# Antilog-NPNO.net
KiCad netlist of a schematic drawn in EAGLE
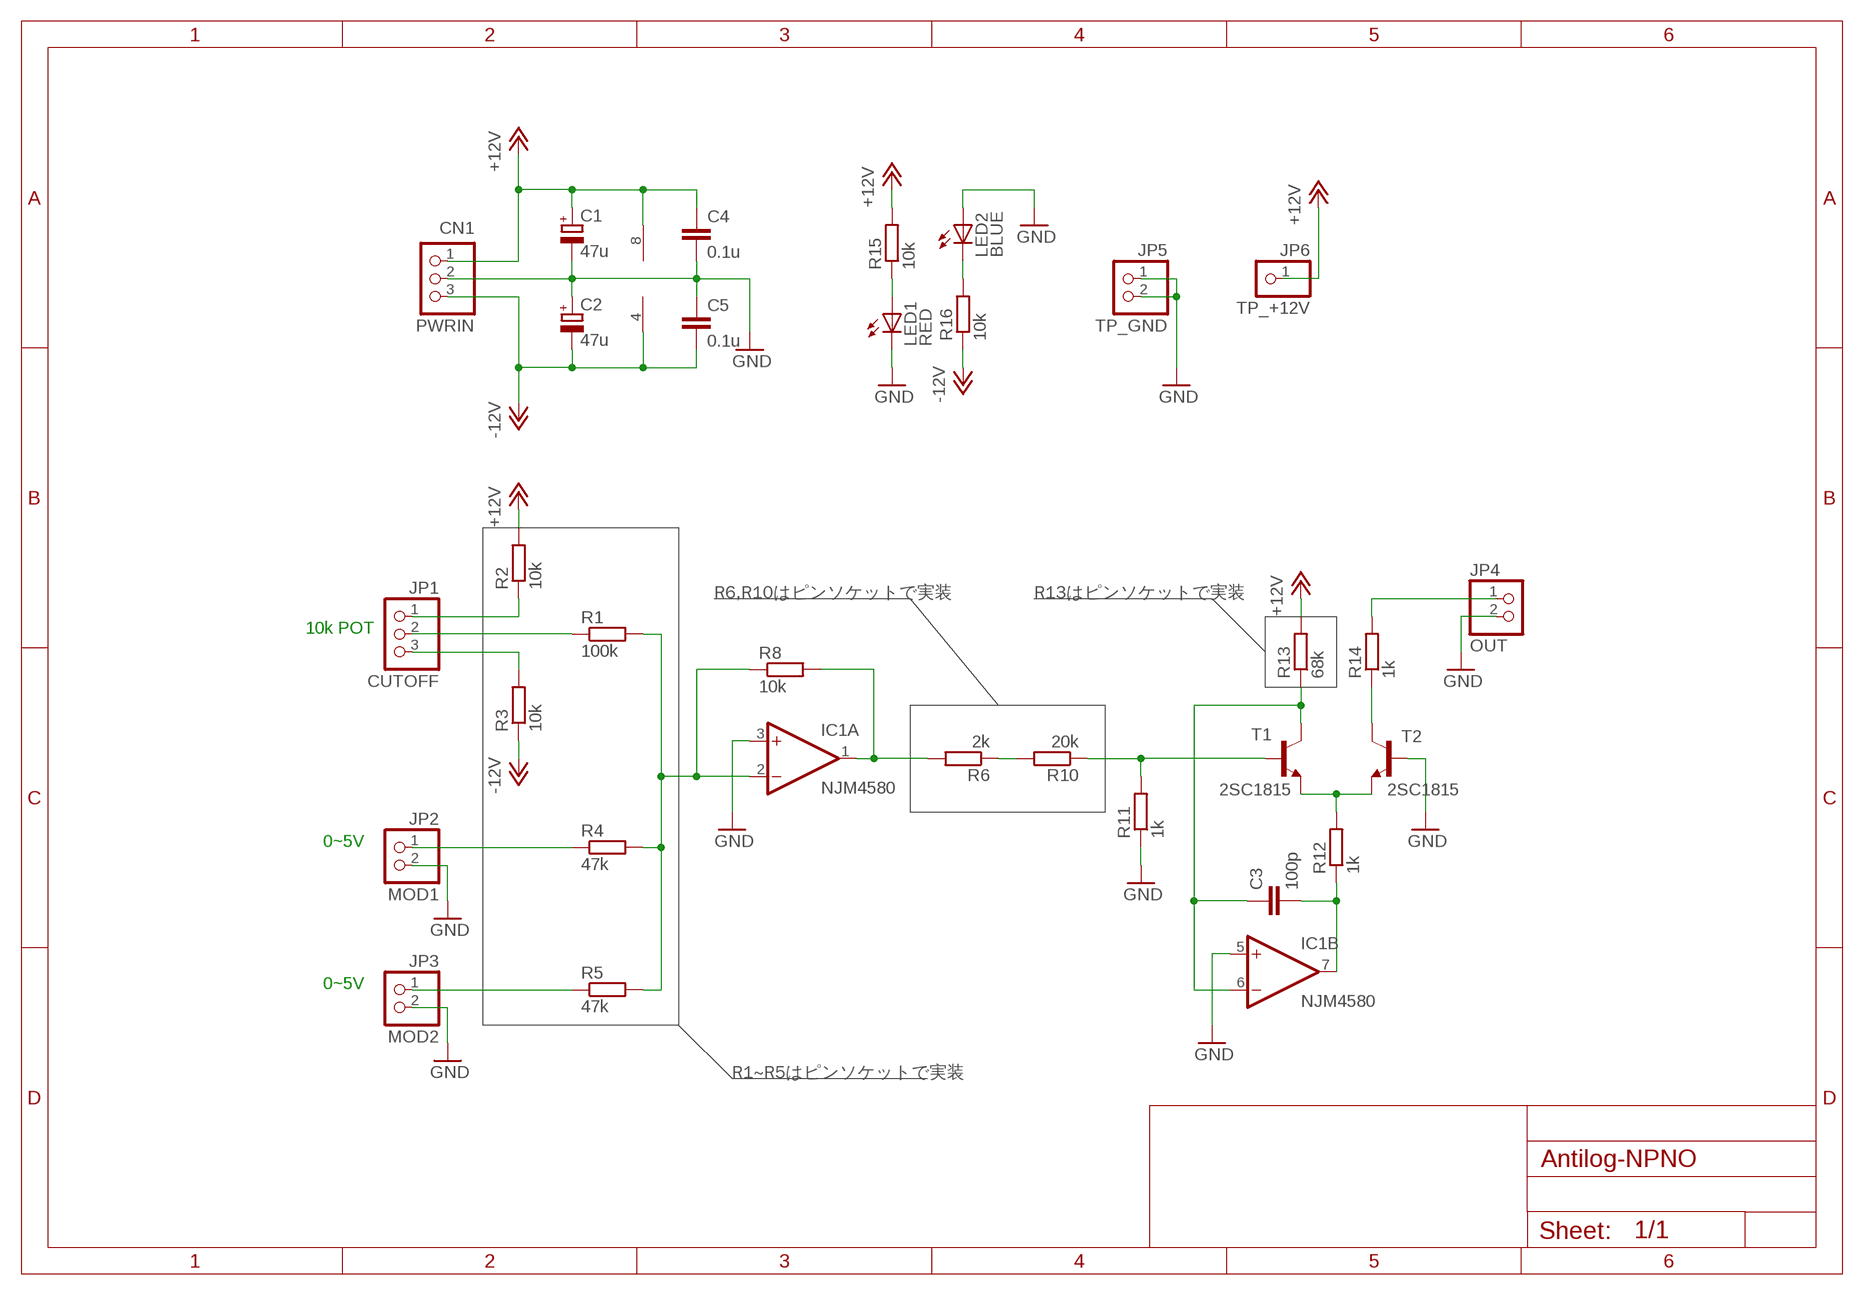
[diagram p0: schematic, sheet 1]

(export (version "E")
  (design (tool "Eeschema 10.0.6"))
  (components
    (comp (ref "C1")
      (value "47u")
      (footprint "eagle-import:E2,5-6")
      (libsource (lib "eagle-import") (part "CPOL-EUE2.5-6"))
    )
    (comp (ref "C2")
      (value "47u")
      (footprint "eagle-import:E2,5-6")
      (libsource (lib "eagle-import") (part "CPOL-EUE2.5-6"))
    )
    (comp (ref "C3")
      (value "100p")
      (footprint "eagle-import:C050-024X044")
      (libsource (lib "eagle-import") (part "C-EU050-024X044"))
    )
    (comp (ref "C4")
      (value "0.1u")
      (footprint "eagle-import:C025-024X044")
      (libsource (lib "eagle-import") (part "C-EU025-024X044"))
    )
    (comp (ref "C5")
      (value "0.1u")
      (footprint "eagle-import:C025-024X044")
      (libsource (lib "eagle-import") (part "C-EU025-024X044"))
    )
    (comp (ref "CN1")
      (value "PWRIN")
      (footprint "eagle-import:B3B-XH-A")
      (libsource (lib "eagle-import") (part "B3B-XH-A"))
    )
    (comp (ref "IC1")
      (value "NJM4580")
      (footprint "eagle-import:DIL08")
      (libsource (lib "eagle-import") (part "4558NLM"))
    )
    (comp (ref "JP1")
      (value "CUTOFF")
      (footprint "eagle-import:1X03")
      (libsource (lib "eagle-import") (part "PINHD-1X3"))
    )
    (comp (ref "JP2")
      (value "MOD1")
      (footprint "eagle-import:1X02")
      (libsource (lib "eagle-import") (part "PINHD-1X2"))
    )
    (comp (ref "JP3")
      (value "MOD2")
      (footprint "eagle-import:1X02")
      (libsource (lib "eagle-import") (part "PINHD-1X2"))
    )
    (comp (ref "JP4")
      (value "OUT")
      (footprint "eagle-import:1X02")
      (libsource (lib "eagle-import") (part "PINHD-1X2"))
    )
    (comp (ref "JP5")
      (value "TP_GND")
      (footprint "eagle-import:1X02")
      (libsource (lib "eagle-import") (part "PINHD-1X2"))
    )
    (comp (ref "JP6")
      (value "TP_+12V")
      (footprint "eagle-import:1X01")
      (libsource (lib "eagle-import") (part "PINHD-1X1"))
    )
    (comp (ref "LED1")
      (value "RED")
      (footprint "eagle-import:LED3MM")
      (libsource (lib "eagle-import") (part "LED3MM"))
    )
    (comp (ref "LED2")
      (value "BLUE")
      (footprint "eagle-import:LED3MM")
      (libsource (lib "eagle-import") (part "LED3MM"))
    )
    (comp (ref "R1")
      (value "100k")
      (footprint "eagle-import:0207_7")
      (libsource (lib "eagle-import") (part "R-EU_0207/7"))
    )
    (comp (ref "R2")
      (value "10k")
      (footprint "eagle-import:0207_7")
      (libsource (lib "eagle-import") (part "R-EU_0207/7"))
    )
    (comp (ref "R3")
      (value "10k")
      (footprint "eagle-import:0207_7")
      (libsource (lib "eagle-import") (part "R-EU_0207/7"))
    )
    (comp (ref "R4")
      (value "47k")
      (footprint "eagle-import:0207_7")
      (libsource (lib "eagle-import") (part "R-EU_0207/7"))
    )
    (comp (ref "R5")
      (value "47k")
      (footprint "eagle-import:0207_7")
      (libsource (lib "eagle-import") (part "R-EU_0207/7"))
    )
    (comp (ref "R6")
      (value "2k")
      (footprint "eagle-import:0207_7")
      (libsource (lib "eagle-import") (part "R-EU_0207/7"))
    )
    (comp (ref "R8")
      (value "10k")
      (footprint "eagle-import:0207_7")
      (libsource (lib "eagle-import") (part "R-EU_0207/7"))
    )
    (comp (ref "R10")
      (value "20k")
      (footprint "eagle-import:0207_7")
      (libsource (lib "eagle-import") (part "R-EU_0207/7"))
    )
    (comp (ref "R11")
      (value "1k")
      (footprint "eagle-import:0207_7")
      (libsource (lib "eagle-import") (part "R-EU_0207/7"))
    )
    (comp (ref "R12")
      (value "1k")
      (footprint "eagle-import:0207_7")
      (libsource (lib "eagle-import") (part "R-EU_0207/7"))
    )
    (comp (ref "R13")
      (value "68k")
      (footprint "eagle-import:0207_7")
      (libsource (lib "eagle-import") (part "R-EU_0207/7"))
    )
    (comp (ref "R14")
      (value "1k")
      (footprint "eagle-import:0207_7")
      (libsource (lib "eagle-import") (part "R-EU_0207/7"))
    )
    (comp (ref "R15")
      (value "10k")
      (footprint "eagle-import:0207_7")
      (libsource (lib "eagle-import") (part "R-EU_0207/7"))
    )
    (comp (ref "R16")
      (value "10k")
      (footprint "eagle-import:0207_7")
      (libsource (lib "eagle-import") (part "R-EU_0207/7"))
    )
    (comp (ref "T1")
      (value "2SC1815")
      (footprint "eagle-import:TO92-ECB")
      (libsource (lib "eagle-import") (part "-NPN-TO92-ECBBC368"))
    )
    (comp (ref "T2")
      (value "2SC1815")
      (footprint "eagle-import:TO92-ECB")
      (libsource (lib "eagle-import") (part "-NPN-TO92-ECBBC368"))
    )
  )
  (nets
    (net (code "1") (name "+12V") (class "Default")
      (node (ref "C1") (pin "+") (pinfunction "+_+") (pintype "passive"))
      (node (ref "C4") (pin "1") (pinfunction "1_1") (pintype "passive"))
      (node (ref "CN1") (pin "1") (pinfunction "1_1") (pintype "passive"))
      (node (ref "IC1") (pin "8") (pinfunction "V+_8") (pintype "power_in"))
      (node (ref "JP6") (pin "1") (pinfunction "1_1") (pintype "passive"))
      (node (ref "R13") (pin "2") (pinfunction "2_2") (pintype "passive"))
      (node (ref "R15") (pin "2") (pinfunction "2_2") (pintype "passive"))
      (node (ref "R2") (pin "2") (pinfunction "2_2") (pintype "passive"))
    )
    (net (code "2") (name "-12V") (class "Default")
      (node (ref "C2") (pin "-") (pinfunction "-_-") (pintype "passive"))
      (node (ref "C5") (pin "2") (pinfunction "2_2") (pintype "passive"))
      (node (ref "CN1") (pin "3") (pinfunction "3_3") (pintype "passive"))
      (node (ref "IC1") (pin "4") (pinfunction "V-_4") (pintype "power_in"))
      (node (ref "R16") (pin "1") (pinfunction "1_1") (pintype "passive"))
      (node (ref "R3") (pin "1") (pinfunction "1_1") (pintype "passive"))
    )
    (net (code "3") (name "GND") (class "Default")
      (node (ref "C1") (pin "-") (pinfunction "-_-") (pintype "passive"))
      (node (ref "C2") (pin "+") (pinfunction "+_+") (pintype "passive"))
      (node (ref "C4") (pin "2") (pinfunction "2_2") (pintype "passive"))
      (node (ref "C5") (pin "1") (pinfunction "1_1") (pintype "passive"))
      (node (ref "CN1") (pin "2") (pinfunction "2_2") (pintype "passive"))
      (node (ref "IC1") (pin "3") (pinfunction "+IN_3") (pintype "input"))
      (node (ref "IC1") (pin "5") (pinfunction "+IN_5") (pintype "input"))
      (node (ref "JP2") (pin "2") (pinfunction "2_2") (pintype "passive"))
      (node (ref "JP3") (pin "2") (pinfunction "2_2") (pintype "passive"))
      (node (ref "JP4") (pin "2") (pinfunction "2_2") (pintype "passive"))
      (node (ref "JP5") (pin "1") (pinfunction "1_1") (pintype "passive"))
      (node (ref "JP5") (pin "2") (pinfunction "2_2") (pintype "passive"))
      (node (ref "LED1") (pin "K") (pinfunction "C_K") (pintype "passive"))
      (node (ref "LED2") (pin "A") (pinfunction "A_A") (pintype "passive"))
      (node (ref "R11") (pin "1") (pinfunction "1_1") (pintype "passive"))
      (node (ref "T2") (pin "B") (pinfunction "B_B") (pintype "passive"))
    )
    (net (code "4") (name "Net-(IC1A--IN)") (class "Default")
      (node (ref "IC1") (pin "2") (pinfunction "-IN_2") (pintype "input"))
      (node (ref "R1") (pin "2") (pinfunction "2_2") (pintype "passive"))
      (node (ref "R4") (pin "2") (pinfunction "2_2") (pintype "passive"))
      (node (ref "R5") (pin "2") (pinfunction "2_2") (pintype "passive"))
      (node (ref "R8") (pin "1") (pinfunction "1_1") (pintype "passive"))
    )
    (net (code "5") (name "Net-(IC1A-OUT)") (class "Default")
      (node (ref "IC1") (pin "1") (pinfunction "OUT_1") (pintype "output"))
      (node (ref "R6") (pin "2") (pinfunction "2_2") (pintype "passive"))
      (node (ref "R8") (pin "2") (pinfunction "2_2") (pintype "passive"))
    )
    (net (code "6") (name "Net-(IC1B--IN)") (class "Default")
      (node (ref "C3") (pin "1") (pinfunction "1_1") (pintype "passive"))
      (node (ref "IC1") (pin "6") (pinfunction "-IN_6") (pintype "input"))
      (node (ref "R13") (pin "1") (pinfunction "1_1") (pintype "passive"))
      (node (ref "T1") (pin "C") (pinfunction "C_C") (pintype "passive"))
    )
    (net (code "7") (name "Net-(IC1B-OUT)") (class "Default")
      (node (ref "C3") (pin "2") (pinfunction "2_2") (pintype "passive"))
      (node (ref "IC1") (pin "7") (pinfunction "OUT_7") (pintype "output"))
      (node (ref "R12") (pin "1") (pinfunction "1_1") (pintype "passive"))
    )
    (net (code "8") (name "Net-(JP1-Pad1)") (class "Default")
      (node (ref "JP1") (pin "1") (pinfunction "1_1") (pintype "passive"))
      (node (ref "R2") (pin "1") (pinfunction "1_1") (pintype "passive"))
    )
    (net (code "9") (name "Net-(JP1-Pad2)") (class "Default")
      (node (ref "JP1") (pin "2") (pinfunction "2_2") (pintype "passive"))
      (node (ref "R1") (pin "1") (pinfunction "1_1") (pintype "passive"))
    )
    (net (code "10") (name "Net-(JP1-Pad3)") (class "Default")
      (node (ref "JP1") (pin "3") (pinfunction "3_3") (pintype "passive"))
      (node (ref "R3") (pin "2") (pinfunction "2_2") (pintype "passive"))
    )
    (net (code "11") (name "Net-(JP2-Pad1)") (class "Default")
      (node (ref "JP2") (pin "1") (pinfunction "1_1") (pintype "passive"))
      (node (ref "R4") (pin "1") (pinfunction "1_1") (pintype "passive"))
    )
    (net (code "12") (name "Net-(JP3-Pad1)") (class "Default")
      (node (ref "JP3") (pin "1") (pinfunction "1_1") (pintype "passive"))
      (node (ref "R5") (pin "1") (pinfunction "1_1") (pintype "passive"))
    )
    (net (code "13") (name "Net-(JP4-Pad1)") (class "Default")
      (node (ref "JP4") (pin "1") (pinfunction "1_1") (pintype "passive"))
      (node (ref "R14") (pin "2") (pinfunction "2_2") (pintype "passive"))
    )
    (net (code "14") (name "Net-(LED1-PadA)") (class "Default")
      (node (ref "LED1") (pin "A") (pinfunction "A_A") (pintype "passive"))
      (node (ref "R15") (pin "1") (pinfunction "1_1") (pintype "passive"))
    )
    (net (code "15") (name "Net-(LED2-C)") (class "Default")
      (node (ref "LED2") (pin "K") (pinfunction "C_K") (pintype "passive"))
      (node (ref "R16") (pin "2") (pinfunction "2_2") (pintype "passive"))
    )
    (net (code "16") (name "Net-(R10-Pad1)") (class "Default")
      (node (ref "R10") (pin "1") (pinfunction "1_1") (pintype "passive"))
      (node (ref "R11") (pin "2") (pinfunction "2_2") (pintype "passive"))
      (node (ref "T1") (pin "B") (pinfunction "B_B") (pintype "passive"))
    )
    (net (code "17") (name "Net-(R10-Pad2)") (class "Default")
      (node (ref "R10") (pin "2") (pinfunction "2_2") (pintype "passive"))
      (node (ref "R6") (pin "1") (pinfunction "1_1") (pintype "passive"))
    )
    (net (code "18") (name "Net-(R12-Pad2)") (class "Default")
      (node (ref "R12") (pin "2") (pinfunction "2_2") (pintype "passive"))
      (node (ref "T1") (pin "E") (pinfunction "E_E") (pintype "passive"))
      (node (ref "T2") (pin "E") (pinfunction "E_E") (pintype "passive"))
    )
    (net (code "19") (name "Net-(R14-Pad1)") (class "Default")
      (node (ref "R14") (pin "1") (pinfunction "1_1") (pintype "passive"))
      (node (ref "T2") (pin "C") (pinfunction "C_C") (pintype "passive"))
    )
  )
)
